# EEPROM_SMD_Breakout_WP_Pin.net
KiCad netlist of a schematic drawn in EAGLE
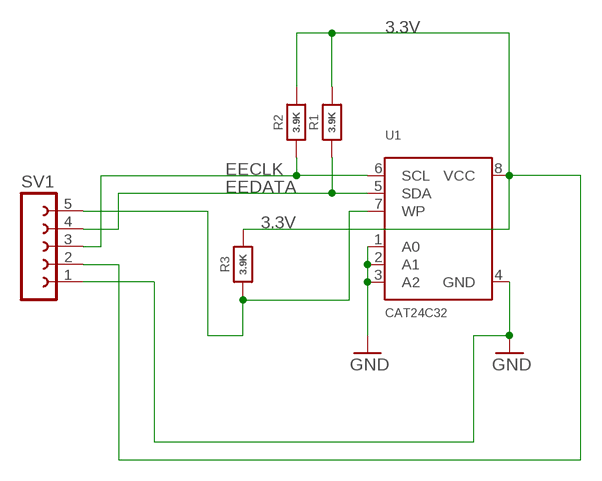
[diagram p0: schematic, sheet 1]

(export (version "E")
  (design (tool "Eeschema 10.0.6"))
  (components
    (comp (ref "R1")
      (value "3.9K")
      (footprint "eagle-import:0805-NO")
      (libsource (lib "eagle-import") (part "RESISTOR0805_NOOUTLINE"))
    )
    (comp (ref "R2")
      (value "3.9K")
      (footprint "eagle-import:0805-NO")
      (libsource (lib "eagle-import") (part "RESISTOR0805_NOOUTLINE"))
    )
    (comp (ref "R3")
      (value "3.9K")
      (footprint "eagle-import:0805-NO")
      (libsource (lib "eagle-import") (part "RESISTOR0805_NOOUTLINE"))
    )
    (comp (ref "SV1")
      (value "FE05-1")
      (footprint "eagle-import:FE05-1")
      (fields (field (name "SPICEPREFIX") "S"))
      (libsource (lib "eagle-import") (part "FE05-1"))
    )
    (comp (ref "U1")
      (value "CAT24C32")
      (footprint "eagle-import:SOIC8_150MIL")
      (libsource (lib "eagle-import") (part "EEPROM_I2C_SOIC8_GENERIC"))
    )
  )
  (nets
    (net (code "1") (name "/3.3V") (class "Default")
      (node (ref "R1") (pin "2") (pinfunction "2_2") (pintype "passive"))
      (node (ref "R2") (pin "2") (pinfunction "2_2") (pintype "passive"))
      (node (ref "R3") (pin "2") (pinfunction "2_2") (pintype "passive"))
      (node (ref "SV1") (pin "2") (pinfunction "2_2") (pintype "passive"))
      (node (ref "U1") (pin "8") (pinfunction "VCC_8") (pintype "power_in"))
    )
    (net (code "2") (name "/EECLK") (class "Default")
      (node (ref "R2") (pin "1") (pinfunction "1_1") (pintype "passive"))
      (node (ref "SV1") (pin "3") (pinfunction "3_3") (pintype "passive"))
      (node (ref "U1") (pin "6") (pinfunction "SCL_6") (pintype "input"))
    )
    (net (code "3") (name "/EEDATA") (class "Default")
      (node (ref "R1") (pin "1") (pinfunction "1_1") (pintype "passive"))
      (node (ref "SV1") (pin "4") (pinfunction "4_4") (pintype "passive"))
      (node (ref "U1") (pin "5") (pinfunction "SDA_5") (pintype "bidirectional"))
    )
    (net (code "4") (name "GND") (class "Default")
      (node (ref "SV1") (pin "1") (pinfunction "1_1") (pintype "passive"))
      (node (ref "U1") (pin "1") (pinfunction "A0_1") (pintype "input"))
      (node (ref "U1") (pin "2") (pinfunction "A1_2") (pintype "input"))
      (node (ref "U1") (pin "3") (pinfunction "A2_3") (pintype "input"))
      (node (ref "U1") (pin "4") (pinfunction "GND_4") (pintype "power_in"))
    )
    (net (code "5") (name "Net-(U1-WP)") (class "Default")
      (node (ref "R3") (pin "1") (pinfunction "1_1") (pintype "passive"))
      (node (ref "SV1") (pin "5") (pinfunction "5_5") (pintype "passive"))
      (node (ref "U1") (pin "7") (pinfunction "WP_7") (pintype "input"))
    )
  )
)
